# TPS7A.net
KiCad netlist of a schematic drawn in EasyEDA Pro
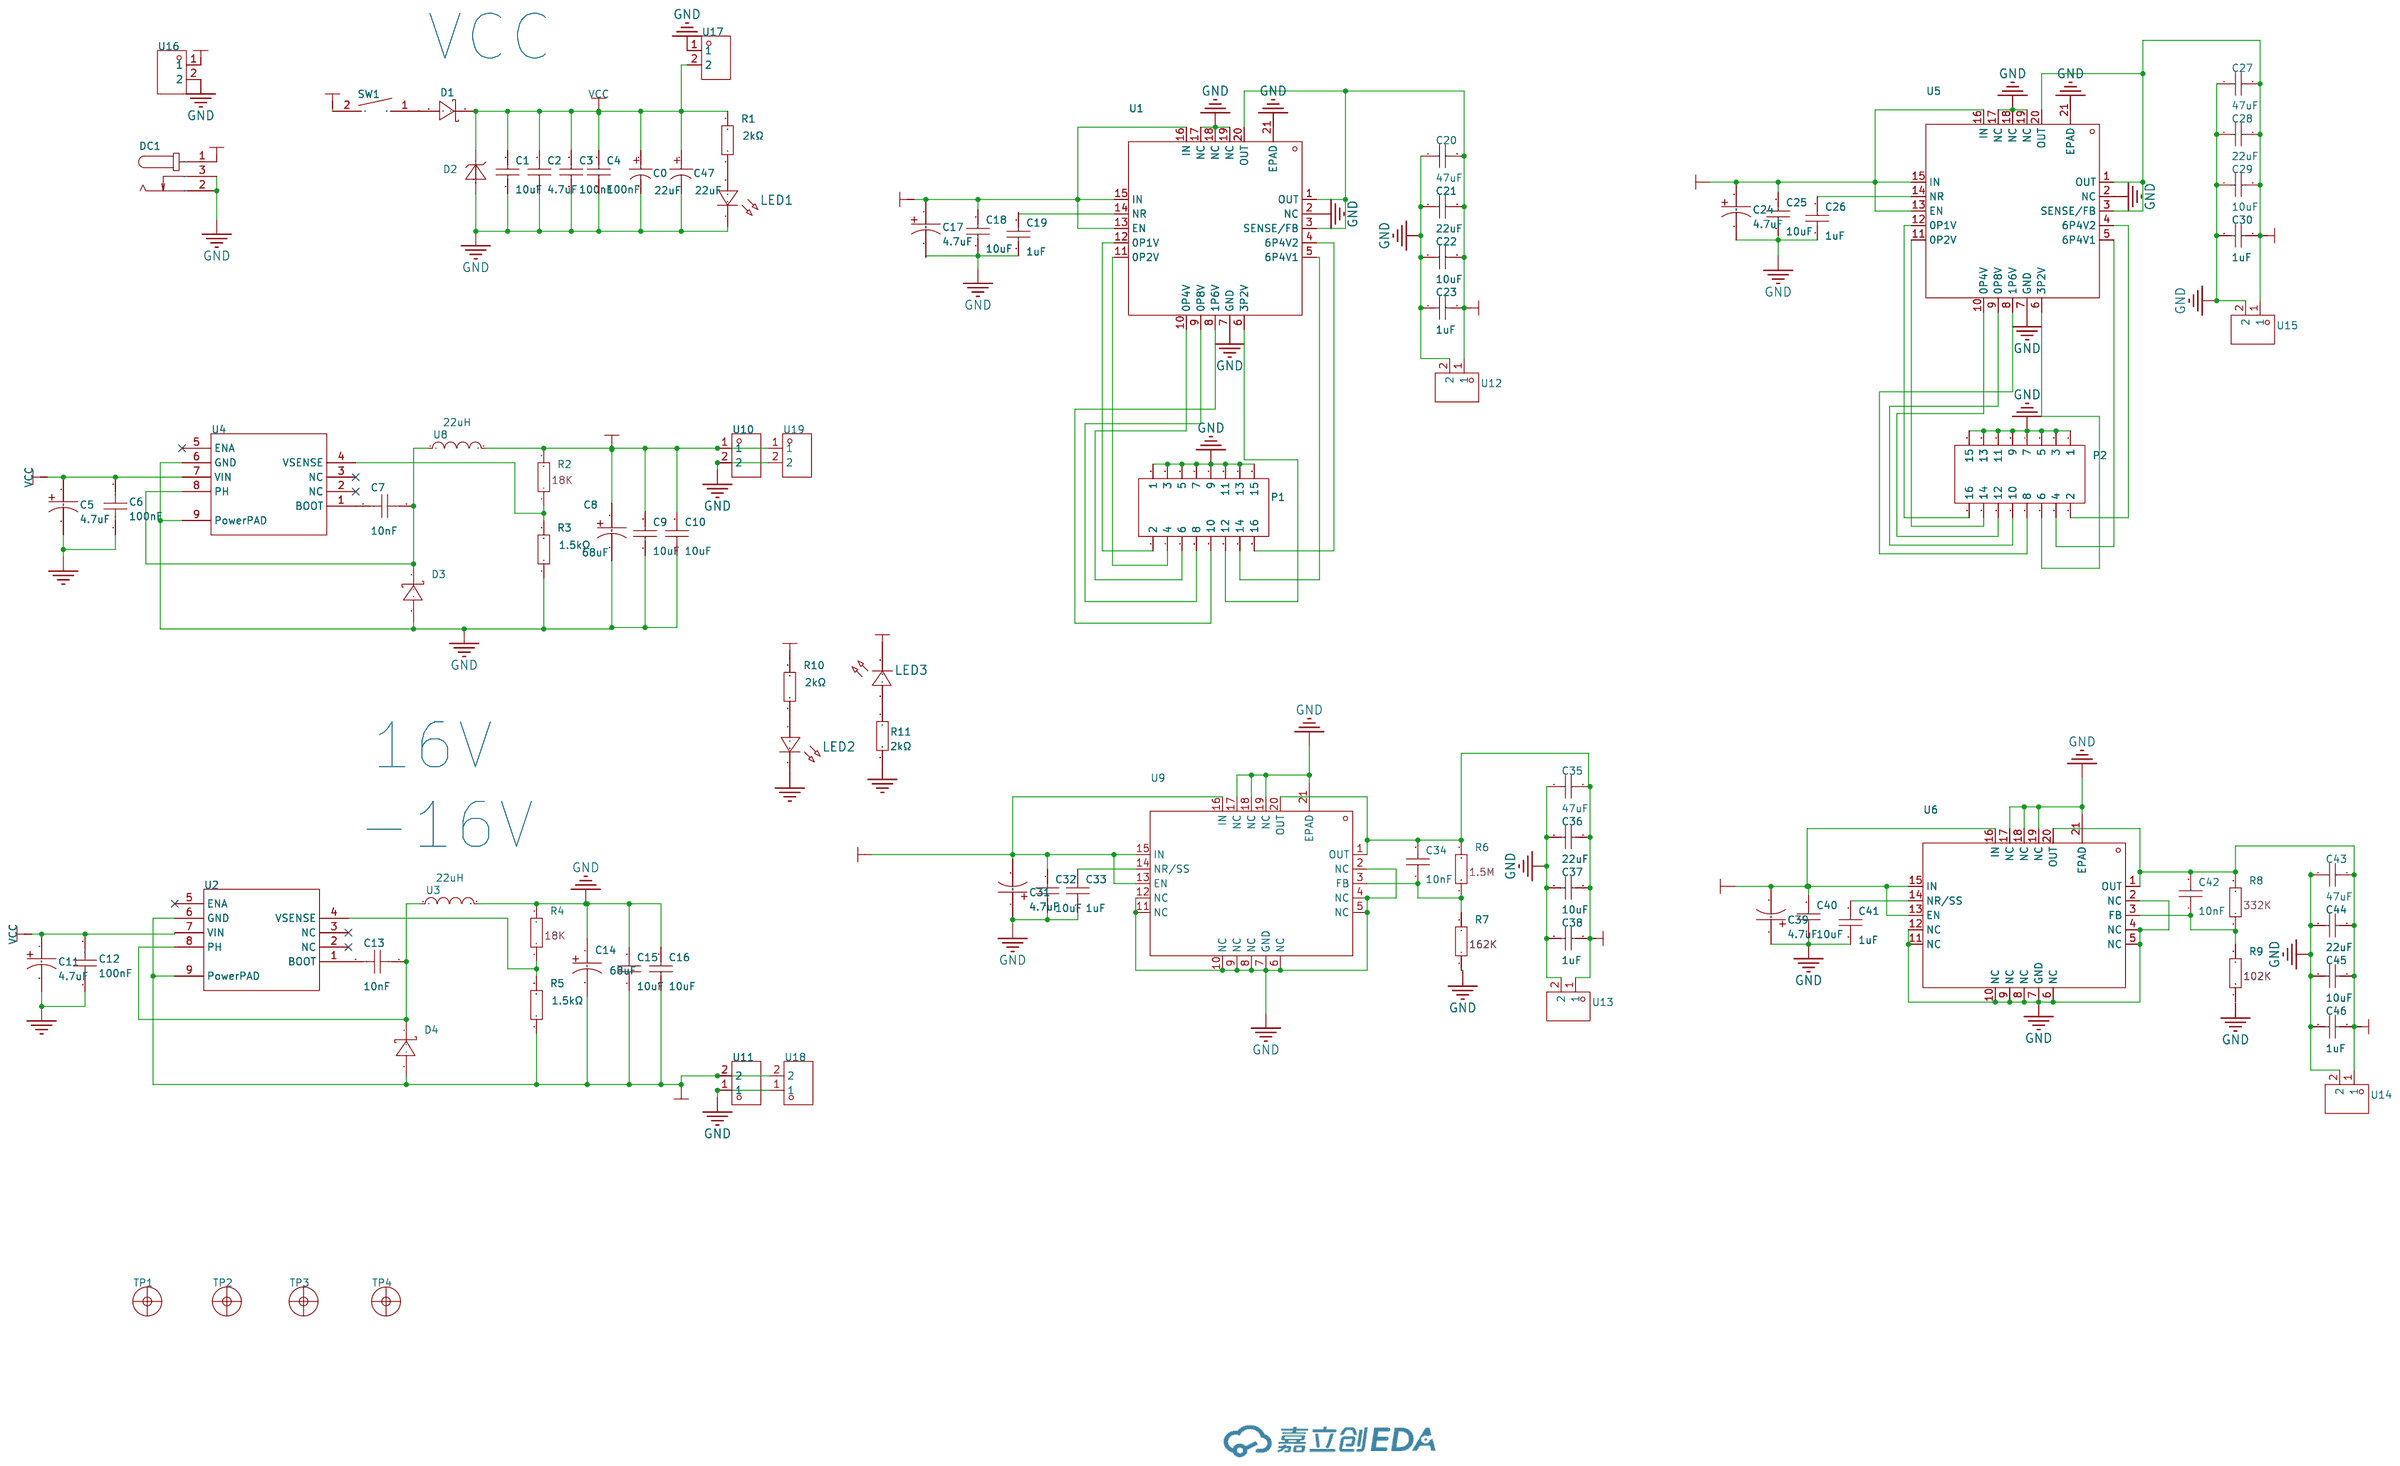
[diagram p0: schematic sheet]

(export (version "E")
  (design (tool "Eeschema 10.0.6"))
  (components
    (comp (ref "C0")
      (value "22uF")
      (footprint "easyedapro:CAP-SMD_BD6.3-L6.6-W6.6-LS7.4-FD")
      (description "容值:22uF;精度:±20%;额定电压:63V;纹波电流:60mA@120Hz;等效串联电阻:-;")
      (fields (field (name "Manufacturer Part") "RT1J220M0607") (field (name "Manufacturer") "ROQANG(容强)"))
      (libsource (lib "easyedapro") (part "RT1J220M0607"))
    )
    (comp (ref "C1")
      (value "10uF")
      (footprint "easyedapro:C0805")
      (description "容值:100nF;精度:±10%;额定电压:50V;材质(温度系数):X7R;")
      (fields (field (name "Manufacturer Part") "0805B104K500NT") (field (name "Manufacturer") "FH(风华)"))
      (libsource (lib "easyedapro") (part "0805B104K500NT"))
    )
    (comp (ref "C2")
      (value "4.7uF")
      (footprint "easyedapro:C0805")
      (description "容值:100nF;精度:±10%;额定电压:50V;材质(温度系数):X7R;")
      (fields (field (name "Manufacturer Part") "0805B104K500NT") (field (name "Manufacturer") "FH(风华)"))
      (libsource (lib "easyedapro") (part "0805B104K500NT"))
    )
    (comp (ref "C3")
      (value "100nF")
      (footprint "easyedapro:C0805")
      (description "容值:100nF;精度:±10%;额定电压:50V;材质(温度系数):X7R;")
      (fields (field (name "Manufacturer Part") "0805B104K500NT") (field (name "Manufacturer") "FH(风华)"))
      (libsource (lib "easyedapro") (part "0805B104K500NT"))
    )
    (comp (ref "C4")
      (value "100nF")
      (footprint "easyedapro:C0805")
      (description "容值:100nF;精度:±10%;额定电压:50V;材质(温度系数):X7R;")
      (fields (field (name "Manufacturer Part") "0805B104K500NT") (field (name "Manufacturer") "FH(风华)"))
      (libsource (lib "easyedapro") (part "0805B104K500NT"))
    )
    (comp (ref "C5")
      (value "4.7uF")
      (footprint "easyedapro:CAP-SMD_BD4.0-L4.3-W4.3-FD-A")
      (description "容值:4.7uF;精度:±20%;额定电压:50V;纹波电流:14mA@120Hz;等效串联电阻:-;")
      (fields (field (name "Manufacturer Part") "VT1H4R7M0405") (field (name "Manufacturer") "ROQANG(容强)"))
      (libsource (lib "easyedapro") (part "VT1H4R7M0405"))
    )
    (comp (ref "C6")
      (value "100nF")
      (footprint "easyedapro:C0805")
      (libsource (lib "easyedapro") (part "CapAcitance"))
    )
    (comp (ref "C7")
      (value "10nF")
      (footprint "easyedapro:C0805")
      (description "容值:10nF;精度:±10%;额定电压:50V;材质(温度系数):X7R;")
      (fields
        (field (name "Manufacturer Part") "CC0805KRX7R9BB103")
        (field (name "Manufacturer") "YAGEO(国巨)")
      )
      (libsource (lib "easyedapro") (part "CC0805KRX7R9BB103"))
    )
    (comp (ref "C8")
      (value "68uF")
      (footprint "easyedapro:CAP-SMD_L7.3-W4.3")
      (description "容值:68uF;精度:±10%;额定电压:25V;等效串联电阻:125mΩ@100kHz;工作温度:-55~+125;")
      (fields
        (field (name "Manufacturer Part") "TPSE686K025R0125")
        (field (name "Manufacturer") "Kyocera AVX")
      )
      (libsource (lib "easyedapro") (part "TPSE686K025R0125"))
    )
    (comp (ref "C9")
      (value "10uF")
      (footprint "easyedapro:C0805")
      (description "容值:100nF;精度:±10%;额定电压:50V;材质(温度系数):X7R;")
      (fields (field (name "Manufacturer Part") "0805B104K500NT") (field (name "Manufacturer") "FH(风华)"))
      (libsource (lib "easyedapro") (part "0805B104K500NT"))
    )
    (comp (ref "C10")
      (value "10uF")
      (footprint "easyedapro:C0805")
      (description "容值:100nF;精度:±10%;额定电压:50V;材质(温度系数):X7R;")
      (fields (field (name "Manufacturer Part") "0805B104K500NT") (field (name "Manufacturer") "FH(风华)"))
      (libsource (lib "easyedapro") (part "0805B104K500NT"))
    )
    (comp (ref "C11")
      (value "4.7uF")
      (footprint "easyedapro:CAP-SMD_BD4.0-L4.3-W4.3-FD-A")
      (description "容值:4.7uF;精度:±20%;额定电压:50V;纹波电流:14mA@120Hz;等效串联电阻:-;")
      (fields (field (name "Manufacturer Part") "VT1H4R7M0405") (field (name "Manufacturer") "ROQANG(容强)"))
      (libsource (lib "easyedapro") (part "VT1H4R7M0405"))
    )
    (comp (ref "C12")
      (value "100nF")
      (footprint "easyedapro:C0805")
      (libsource (lib "easyedapro") (part "CapAcitance"))
    )
    (comp (ref "C13")
      (value "10nF")
      (footprint "easyedapro:C0805")
      (description "容值:10nF;精度:±10%;额定电压:50V;材质(温度系数):X7R;")
      (fields
        (field (name "Manufacturer Part") "CC0805KRX7R9BB103")
        (field (name "Manufacturer") "YAGEO(国巨)")
      )
      (libsource (lib "easyedapro") (part "CC0805KRX7R9BB103"))
    )
    (comp (ref "C14")
      (value "68uF")
      (footprint "easyedapro:CAP-SMD_L7.3-W4.3")
      (description "容值:68uF;精度:±10%;额定电压:25V;等效串联电阻:125mΩ@100kHz;工作温度:-55~+125;")
      (fields
        (field (name "Manufacturer Part") "TPSE686K025R0125")
        (field (name "Manufacturer") "Kyocera AVX")
      )
      (libsource (lib "easyedapro") (part "TPSE686K025R0125"))
    )
    (comp (ref "C15")
      (value "10uF")
      (footprint "easyedapro:C0805")
      (description "容值:100nF;精度:±10%;额定电压:50V;材质(温度系数):X7R;")
      (fields (field (name "Manufacturer Part") "0805B104K500NT") (field (name "Manufacturer") "FH(风华)"))
      (libsource (lib "easyedapro") (part "0805B104K500NT"))
    )
    (comp (ref "C16")
      (value "10uF")
      (footprint "easyedapro:C0805")
      (description "容值:100nF;精度:±10%;额定电压:50V;材质(温度系数):X7R;")
      (fields (field (name "Manufacturer Part") "0805B104K500NT") (field (name "Manufacturer") "FH(风华)"))
      (libsource (lib "easyedapro") (part "0805B104K500NT"))
    )
    (comp (ref "C17")
      (value "4.7uF")
      (footprint "easyedapro:CAP-SMD_BD4.0-L4.3-W4.3-FD-A")
      (description "容值:4.7uF;精度:±20%;额定电压:50V;纹波电流:14mA@120Hz;等效串联电阻:-;")
      (fields (field (name "Manufacturer Part") "VT1H4R7M0405") (field (name "Manufacturer") "ROQANG(容强)"))
      (libsource (lib "easyedapro") (part "VT1H4R7M0405"))
    )
    (comp (ref "C18")
      (value "10uF")
      (footprint "easyedapro:C0805")
      (description "容值:100nF;精度:±10%;额定电压:50V;材质(温度系数):X7R;")
      (fields (field (name "Manufacturer Part") "0805B104K500NT") (field (name "Manufacturer") "FH(风华)"))
      (libsource (lib "easyedapro") (part "0805B104K500NT"))
    )
    (comp (ref "C19")
      (value "1uF")
      (footprint "easyedapro:C0805")
      (description "容值:100nF;精度:±10%;额定电压:50V;材质(温度系数):X7R;")
      (fields (field (name "Manufacturer Part") "0805B104K500NT") (field (name "Manufacturer") "FH(风华)"))
      (libsource (lib "easyedapro") (part "0805B104K500NT"))
    )
    (comp (ref "C20")
      (value "47uF")
      (footprint "easyedapro:C0805")
      (description "容值:100nF;精度:±10%;额定电压:50V;材质(温度系数):X7R;")
      (fields (field (name "Manufacturer Part") "0805B104K500NT") (field (name "Manufacturer") "FH(风华)"))
      (libsource (lib "easyedapro") (part "0805B104K500NT"))
    )
    (comp (ref "C21")
      (value "22uF")
      (footprint "easyedapro:C0805")
      (description "容值:100nF;精度:±10%;额定电压:50V;材质(温度系数):X7R;")
      (fields (field (name "Manufacturer Part") "0805B104K500NT") (field (name "Manufacturer") "FH(风华)"))
      (libsource (lib "easyedapro") (part "0805B104K500NT"))
    )
    (comp (ref "C22")
      (value "10uF")
      (footprint "easyedapro:C0805")
      (description "容值:100nF;精度:±10%;额定电压:50V;材质(温度系数):X7R;")
      (fields (field (name "Manufacturer Part") "0805B104K500NT") (field (name "Manufacturer") "FH(风华)"))
      (libsource (lib "easyedapro") (part "0805B104K500NT"))
    )
    (comp (ref "C23")
      (value "1uF")
      (footprint "easyedapro:C0805")
      (description "容值:100nF;精度:±10%;额定电压:50V;材质(温度系数):X7R;")
      (fields (field (name "Manufacturer Part") "0805B104K500NT") (field (name "Manufacturer") "FH(风华)"))
      (libsource (lib "easyedapro") (part "0805B104K500NT"))
    )
    (comp (ref "C24")
      (value "4.7uF")
      (footprint "easyedapro:CAP-SMD_BD4.0-L4.3-W4.3-FD-A")
      (description "容值:4.7uF;精度:±20%;额定电压:50V;纹波电流:14mA@120Hz;等效串联电阻:-;")
      (fields (field (name "Manufacturer Part") "VT1H4R7M0405") (field (name "Manufacturer") "ROQANG(容强)"))
      (libsource (lib "easyedapro") (part "VT1H4R7M0405"))
    )
    (comp (ref "C25")
      (value "10uF")
      (footprint "easyedapro:C0805")
      (description "容值:100nF;精度:±10%;额定电压:50V;材质(温度系数):X7R;")
      (fields (field (name "Manufacturer Part") "0805B104K500NT") (field (name "Manufacturer") "FH(风华)"))
      (libsource (lib "easyedapro") (part "0805B104K500NT"))
    )
    (comp (ref "C26")
      (value "1uF")
      (footprint "easyedapro:C0805")
      (description "容值:100nF;精度:±10%;额定电压:50V;材质(温度系数):X7R;")
      (fields (field (name "Manufacturer Part") "0805B104K500NT") (field (name "Manufacturer") "FH(风华)"))
      (libsource (lib "easyedapro") (part "0805B104K500NT"))
    )
    (comp (ref "C27")
      (value "47uF")
      (footprint "easyedapro:C0805")
      (description "容值:100nF;精度:±10%;额定电压:50V;材质(温度系数):X7R;")
      (fields (field (name "Manufacturer Part") "0805B104K500NT") (field (name "Manufacturer") "FH(风华)"))
      (libsource (lib "easyedapro") (part "0805B104K500NT"))
    )
    (comp (ref "C28")
      (value "22uF")
      (footprint "easyedapro:C0805")
      (description "容值:100nF;精度:±10%;额定电压:50V;材质(温度系数):X7R;")
      (fields (field (name "Manufacturer Part") "0805B104K500NT") (field (name "Manufacturer") "FH(风华)"))
      (libsource (lib "easyedapro") (part "0805B104K500NT"))
    )
    (comp (ref "C29")
      (value "10uF")
      (footprint "easyedapro:C0805")
      (description "容值:100nF;精度:±10%;额定电压:50V;材质(温度系数):X7R;")
      (fields (field (name "Manufacturer Part") "0805B104K500NT") (field (name "Manufacturer") "FH(风华)"))
      (libsource (lib "easyedapro") (part "0805B104K500NT"))
    )
    (comp (ref "C30")
      (value "1uF")
      (footprint "easyedapro:C0805")
      (description "容值:100nF;精度:±10%;额定电压:50V;材质(温度系数):X7R;")
      (fields (field (name "Manufacturer Part") "0805B104K500NT") (field (name "Manufacturer") "FH(风华)"))
      (libsource (lib "easyedapro") (part "0805B104K500NT"))
    )
    (comp (ref "C31")
      (value "4.7uF")
      (footprint "easyedapro:CAP-SMD_BD4.0-L4.3-W4.3-FD-A")
      (description "容值:4.7uF;精度:±20%;额定电压:50V;纹波电流:14mA@120Hz;等效串联电阻:-;")
      (fields (field (name "Manufacturer Part") "VT1H4R7M0405") (field (name "Manufacturer") "ROQANG(容强)"))
      (libsource (lib "easyedapro") (part "VT1H4R7M0405"))
    )
    (comp (ref "C32")
      (value "10uF")
      (footprint "easyedapro:C0805")
      (description "容值:100nF;精度:±10%;额定电压:50V;材质(温度系数):X7R;")
      (fields (field (name "Manufacturer Part") "0805B104K500NT") (field (name "Manufacturer") "FH(风华)"))
      (libsource (lib "easyedapro") (part "0805B104K500NT"))
    )
    (comp (ref "C33")
      (value "1uF")
      (footprint "easyedapro:C0805")
      (description "容值:100nF;精度:±10%;额定电压:50V;材质(温度系数):X7R;")
      (fields (field (name "Manufacturer Part") "0805B104K500NT") (field (name "Manufacturer") "FH(风华)"))
      (libsource (lib "easyedapro") (part "0805B104K500NT"))
    )
    (comp (ref "C34")
      (value "10nF")
      (footprint "easyedapro:C0805")
      (description "容值:100nF;精度:±10%;额定电压:50V;材质(温度系数):X7R;")
      (fields (field (name "Manufacturer Part") "0805B104K500NT") (field (name "Manufacturer") "FH(风华)"))
      (libsource (lib "easyedapro") (part "0805B104K500NT"))
    )
    (comp (ref "C35")
      (value "47uF")
      (footprint "easyedapro:C0805")
      (description "容值:100nF;精度:±10%;额定电压:50V;材质(温度系数):X7R;")
      (fields (field (name "Manufacturer Part") "0805B104K500NT") (field (name "Manufacturer") "FH(风华)"))
      (libsource (lib "easyedapro") (part "0805B104K500NT"))
    )
    (comp (ref "C36")
      (value "22uF")
      (footprint "easyedapro:C0805")
      (description "容值:100nF;精度:±10%;额定电压:50V;材质(温度系数):X7R;")
      (fields (field (name "Manufacturer Part") "0805B104K500NT") (field (name "Manufacturer") "FH(风华)"))
      (libsource (lib "easyedapro") (part "0805B104K500NT"))
    )
    (comp (ref "C37")
      (value "10uF")
      (footprint "easyedapro:C0805")
      (description "容值:100nF;精度:±10%;额定电压:50V;材质(温度系数):X7R;")
      (fields (field (name "Manufacturer Part") "0805B104K500NT") (field (name "Manufacturer") "FH(风华)"))
      (libsource (lib "easyedapro") (part "0805B104K500NT"))
    )
    (comp (ref "C38")
      (value "1uF")
      (footprint "easyedapro:C0805")
      (description "容值:100nF;精度:±10%;额定电压:50V;材质(温度系数):X7R;")
      (fields (field (name "Manufacturer Part") "0805B104K500NT") (field (name "Manufacturer") "FH(风华)"))
      (libsource (lib "easyedapro") (part "0805B104K500NT"))
    )
    (comp (ref "C39")
      (value "4.7uF")
      (footprint "easyedapro:CAP-SMD_BD4.0-L4.3-W4.3-FD-A")
      (description "容值:4.7uF;精度:±20%;额定电压:50V;纹波电流:14mA@120Hz;等效串联电阻:-;")
      (fields (field (name "Manufacturer Part") "VT1H4R7M0405") (field (name "Manufacturer") "ROQANG(容强)"))
      (libsource (lib "easyedapro") (part "VT1H4R7M0405"))
    )
    (comp (ref "C40")
      (value "10uF")
      (footprint "easyedapro:C0805")
      (description "容值:100nF;精度:±10%;额定电压:50V;材质(温度系数):X7R;")
      (fields (field (name "Manufacturer Part") "0805B104K500NT") (field (name "Manufacturer") "FH(风华)"))
      (libsource (lib "easyedapro") (part "0805B104K500NT"))
    )
    (comp (ref "C41")
      (value "1uF")
      (footprint "easyedapro:C0805")
      (description "容值:100nF;精度:±10%;额定电压:50V;材质(温度系数):X7R;")
      (fields (field (name "Manufacturer Part") "0805B104K500NT") (field (name "Manufacturer") "FH(风华)"))
      (libsource (lib "easyedapro") (part "0805B104K500NT"))
    )
    (comp (ref "C42")
      (value "10nF")
      (footprint "easyedapro:C0805")
      (description "容值:100nF;精度:±10%;额定电压:50V;材质(温度系数):X7R;")
      (fields (field (name "Manufacturer Part") "0805B104K500NT") (field (name "Manufacturer") "FH(风华)"))
      (libsource (lib "easyedapro") (part "0805B104K500NT"))
    )
    (comp (ref "C43")
      (value "47uF")
      (footprint "easyedapro:C0805")
      (description "容值:100nF;精度:±10%;额定电压:50V;材质(温度系数):X7R;")
      (fields (field (name "Manufacturer Part") "0805B104K500NT") (field (name "Manufacturer") "FH(风华)"))
      (libsource (lib "easyedapro") (part "0805B104K500NT"))
    )
    (comp (ref "C44")
      (value "22uF")
      (footprint "easyedapro:C0805")
      (description "容值:100nF;精度:±10%;额定电压:50V;材质(温度系数):X7R;")
      (fields (field (name "Manufacturer Part") "0805B104K500NT") (field (name "Manufacturer") "FH(风华)"))
      (libsource (lib "easyedapro") (part "0805B104K500NT"))
    )
    (comp (ref "C45")
      (value "10uF")
      (footprint "easyedapro:C0805")
      (description "容值:100nF;精度:±10%;额定电压:50V;材质(温度系数):X7R;")
      (fields (field (name "Manufacturer Part") "0805B104K500NT") (field (name "Manufacturer") "FH(风华)"))
      (libsource (lib "easyedapro") (part "0805B104K500NT"))
    )
    (comp (ref "C46")
      (value "1uF")
      (footprint "easyedapro:C0805")
      (description "容值:100nF;精度:±10%;额定电压:50V;材质(温度系数):X7R;")
      (fields (field (name "Manufacturer Part") "0805B104K500NT") (field (name "Manufacturer") "FH(风华)"))
      (libsource (lib "easyedapro") (part "0805B104K500NT"))
    )
    (comp (ref "C47")
      (value "22uF")
      (footprint "easyedapro:CAP-SMD_BD6.3-L6.6-W6.6-LS7.4-FD")
      (description "容值:22uF;精度:±20%;额定电压:63V;纹波电流:60mA@120Hz;等效串联电阻:-;")
      (fields (field (name "Manufacturer Part") "RT1J220M0607") (field (name "Manufacturer") "ROQANG(容强)"))
      (libsource (lib "easyedapro") (part "RT1J220M0607"))
    )
    (comp (ref "D1")
      (value "B340A")
      (footprint "easyedapro:SMA_L4.3-W2.6-LS5.2-RD")
      (description "直流反向耐压(Vr):40V;平均整流电流(Io):3A;正向压降(Vf):550mV@3A;")
      (fields (field (name "Manufacturer") "MDD"))
      (libsource (lib "easyedapro") (part "B340A"))
    )
    (comp (ref "D2")
      (value "SMBJ30A")
      (footprint "easyedapro:SMB_L4.4-W3.6-LS5.3-RD")
      (description "极性:单向;反向截止电压(Vrwm):30V;击穿电压:33.3V;反向漏电流(Ir):5uA;峰值脉冲电流(Ipp)@10/1000s:12.4A;最大钳位电压:48.4V;")
      (fields (field (name "Manufacturer") "GOODWORK(固得沃克)"))
      (libsource (lib "easyedapro") (part "SMBJ30A_C908803"))
    )
    (comp (ref "D3")
      (value "B340A")
      (footprint "easyedapro:SMA_L4.3-W2.6-LS5.2-RD")
      (description "直流反向耐压(Vr):40V;平均整流电流(Io):3A;正向压降(Vf):550mV@3A;")
      (fields (field (name "Manufacturer") "MDD"))
      (libsource (lib "easyedapro") (part "B340A"))
    )
    (comp (ref "D4")
      (value "B340A")
      (footprint "easyedapro:SMA_L4.3-W2.6-LS5.2-RD")
      (description "直流反向耐压(Vr):40V;平均整流电流(Io):3A;正向压降(Vf):550mV@3A;")
      (fields (field (name "Manufacturer") "MDD"))
      (libsource (lib "easyedapro") (part "B340A"))
    )
    (comp (ref "DC1")
      (value "DC005")
      (footprint "easyedapro:DC-IN-TH_DC005")
      (description "连接器类型:DC电源插座;安装方式:弯插;触点内径:2mm;触点外径:6.3mm;额定电流:500mA;额定电压:30V;工作温度范围:-40~+55;")
      (fields (field (name "Manufacturer") "SHOU HAN(首韩)"))
      (libsource (lib "easyedapro") (part "DC005_C431533"))
    )
    (comp (ref "LED1")
      (value "~")
      (footprint "easyedapro:LED_0805")
      (libsource (lib "easyedapro") (part "LED_R"))
    )
    (comp (ref "LED2")
      (value "~")
      (footprint "easyedapro:LED_0805")
      (libsource (lib "easyedapro") (part "LED_R"))
    )
    (comp (ref "LED3")
      (value "~")
      (footprint "easyedapro:LED_0805")
      (libsource (lib "easyedapro") (part "LED_R"))
    )
    (comp (ref "P1")
      (value "2.54-2*8P针")
      (footprint "easyedapro:HDR-TH_16P-P2.54-V-M-R2-C8-S2.54")
      (fields (field (name "Manufacturer") "BOOMELE(博穆精密)"))
      (libsource (lib "easyedapro") (part "Header-Male-2.54_2x8"))
    )
    (comp (ref "P2")
      (value "2.54-2*8P针")
      (footprint "easyedapro:HDR-TH_16P-P2.54-V-M-R2-C8-S2.54")
      (fields (field (name "Manufacturer") "BOOMELE(博穆精密)"))
      (libsource (lib "easyedapro") (part "Header-Male-2.54_2x8"))
    )
    (comp (ref "R1")
      (value "2kΩ")
      (footprint "easyedapro:R0805")
      (description "电阻类型:厚膜电阻;阻值:10kΩ;精度:±1%;功率:125mW;温度系数:±100ppm/;最大工作电压:150V;工作温度范围:-55~+155;")
      (fields
        (field (name "Manufacturer Part") "0805W8F1002T5E")
        (field (name "Manufacturer") "UNI-ROYAL(厚声)")
      )
      (libsource (lib "easyedapro") (part "0805W8F1002T5E"))
    )
    (comp (ref "R2")
      (value "0805W8F9101T5E")
      (footprint "easyedapro:R0805")
      (description "18K")
      (fields (field (name "Manufacturer") "UNI-ROYAL(厚声)"))
      (libsource (lib "easyedapro") (part "0805W8F9101T5E"))
    )
    (comp (ref "R3")
      (value "1.5kΩ")
      (footprint "easyedapro:R0805")
      (description "电阻类型:厚膜电阻;阻值:3kΩ;精度:±1%;功率:125mW;温度系数:±100ppm/;最大工作电压:150V;工作温度范围:-55~+155;")
      (fields
        (field (name "Manufacturer Part") "0805W8F3001T5E")
        (field (name "Manufacturer") "UNI-ROYAL(厚声)")
      )
      (libsource (lib "easyedapro") (part "0805W8F3001T5E"))
    )
    (comp (ref "R4")
      (value "0805W8F9101T5E")
      (footprint "easyedapro:R0805")
      (description "18K")
      (fields (field (name "Manufacturer") "UNI-ROYAL(厚声)"))
      (libsource (lib "easyedapro") (part "0805W8F9101T5E"))
    )
    (comp (ref "R5")
      (value "1.5kΩ")
      (footprint "easyedapro:R0805")
      (description "电阻类型:厚膜电阻;阻值:3kΩ;精度:±1%;功率:125mW;温度系数:±100ppm/;最大工作电压:150V;工作温度范围:-55~+155;")
      (fields
        (field (name "Manufacturer Part") "0805W8F3001T5E")
        (field (name "Manufacturer") "UNI-ROYAL(厚声)")
      )
      (libsource (lib "easyedapro") (part "0805W8F3001T5E"))
    )
    (comp (ref "R6")
      (value "0805W8F9101T5E")
      (footprint "easyedapro:R0805")
      (description "1.5M")
      (fields (field (name "Manufacturer") "UNI-ROYAL(厚声)"))
      (libsource (lib "easyedapro") (part "0805W8F9101T5E"))
    )
    (comp (ref "R7")
      (value "0805W8F9101T5E")
      (footprint "easyedapro:R0805")
      (description "162K")
      (fields (field (name "Manufacturer") "UNI-ROYAL(厚声)"))
      (libsource (lib "easyedapro") (part "0805W8F9101T5E"))
    )
    (comp (ref "R8")
      (value "0805W8F9101T5E")
      (footprint "easyedapro:R0805")
      (description "332K")
      (fields (field (name "Manufacturer") "UNI-ROYAL(厚声)"))
      (libsource (lib "easyedapro") (part "0805W8F9101T5E"))
    )
    (comp (ref "R9")
      (value "0805W8F9101T5E")
      (footprint "easyedapro:R0805")
      (description "102K")
      (fields (field (name "Manufacturer") "UNI-ROYAL(厚声)"))
      (libsource (lib "easyedapro") (part "0805W8F9101T5E"))
    )
    (comp (ref "R10")
      (value "2kΩ")
      (footprint "easyedapro:R0805")
      (description "电阻类型:厚膜电阻;阻值:10kΩ;精度:±1%;功率:125mW;温度系数:±100ppm/;最大工作电压:150V;工作温度范围:-55~+155;")
      (fields
        (field (name "Manufacturer Part") "0805W8F1002T5E")
        (field (name "Manufacturer") "UNI-ROYAL(厚声)")
      )
      (libsource (lib "easyedapro") (part "0805W8F1002T5E"))
    )
    (comp (ref "R11")
      (value "2kΩ")
      (footprint "easyedapro:R0805")
      (description "电阻类型:厚膜电阻;阻值:10kΩ;精度:±1%;功率:125mW;温度系数:±100ppm/;最大工作电压:150V;工作温度范围:-55~+155;")
      (fields
        (field (name "Manufacturer Part") "0805W8F1002T5E")
        (field (name "Manufacturer") "UNI-ROYAL(厚声)")
      )
      (libsource (lib "easyedapro") (part "0805W8F1002T5E"))
    )
    (comp (ref "SW1")
      (value "RS601HL-1010011BB")
      (footprint "easyedapro:SW-TH_RS601HL-1010011BB")
      (fields (field (name "Manufacturer") "HCTL(华灿天禄)"))
      (libsource (lib "easyedapro") (part "RS601HL-1010011BB"))
    )
    (comp (ref "TP1") (value "~") (footprint "easyedapro:M3") (libsource (lib "easyedapro") (part "M3")))
    (comp (ref "TP2") (value "~") (footprint "easyedapro:M3") (libsource (lib "easyedapro") (part "M3")))
    (comp (ref "TP3") (value "~") (footprint "easyedapro:M3") (libsource (lib "easyedapro") (part "M3")))
    (comp (ref "TP4") (value "~") (footprint "easyedapro:M3") (libsource (lib "easyedapro") (part "M3")))
    (comp (ref "U1")
      (value "TPS7A4701RGWR")
      (footprint "easyedapro:VQFN-20_L5.0-W5.0-P0.65-TL-EP")
      (description "输出类型:可调;输出极性:正;最大输入电压:35V;输出电压:1.4V~34V;输出电流:1A;电源纹波抑制比(PSRR):78dB@(1kHz);")
      (fields (field (name "Manufacturer") "TI(德州仪器)"))
      (libsource (lib "easyedapro") (part "TPS7A4701RGWR"))
    )
    (comp (ref "U2")
      (value "TPS5430DDAR")
      (footprint "easyedapro:SOIC-8_L5.0-W4.0-P1.27-LS6.0-BL-EP2.0")
      (description "功能类型:降压型;同步整流:-;输出通道数:-;拓扑结构:-;输入电压:-;输出电流(最大值):-;开关频率:-;")
      (fields (field (name "Manufacturer") "TI(德州仪器)"))
      (libsource (lib "easyedapro") (part "TPS5430DDAR"))
    )
    (comp (ref "U3")
      (value "22uH")
      (footprint "easyedapro:IND-SMD_L7.0-W6.6")
      (description "电感值:6.8uH;精度:±20%;")
      (fields (field (name "Manufacturer Part") "XR0650-6R8M") (field (name "Manufacturer") "XR(祥如)"))
      (libsource (lib "easyedapro") (part "XR0650-6R8M"))
    )
    (comp (ref "U4")
      (value "TPS5430DDAR")
      (footprint "easyedapro:SOIC-8_L5.0-W4.0-P1.27-LS6.0-BL-EP2.0")
      (description "功能类型:降压型;同步整流:-;输出通道数:-;拓扑结构:-;输入电压:-;输出电流(最大值):-;开关频率:-;")
      (fields (field (name "Manufacturer") "TI(德州仪器)"))
      (libsource (lib "easyedapro") (part "TPS5430DDAR"))
    )
    (comp (ref "U5")
      (value "TPS7A4701RGWR")
      (footprint "easyedapro:VQFN-20_L5.0-W5.0-P0.65-TL-EP")
      (description "输出类型:可调;输出极性:正;最大输入电压:35V;输出电压:1.4V~34V;输出电流:1A;电源纹波抑制比(PSRR):78dB@(1kHz);")
      (fields (field (name "Manufacturer") "TI(德州仪器)"))
      (libsource (lib "easyedapro") (part "TPS7A4701RGWR"))
    )
    (comp (ref "U6")
      (value "TPS7A3301RGWR")
      (footprint "easyedapro:VQFN-20_L5.0-W5.0-P0.65-TL-EP")
      (description "输出类型:可调;输出极性:负;最大输入电压:36V;输出电压:1.18V~33V;输出电流:1A;电源纹波抑制比(PSRR):72dB@(10kHz);")
      (fields (field (name "Manufacturer") "TI(德州仪器)"))
      (libsource (lib "easyedapro") (part "TPS7A3301RGWR"))
    )
    (comp (ref "U8")
      (value "22uH")
      (footprint "easyedapro:IND-SMD_L7.0-W6.6")
      (description "电感值:6.8uH;精度:±20%;")
      (fields (field (name "Manufacturer Part") "XR0650-6R8M") (field (name "Manufacturer") "XR(祥如)"))
      (libsource (lib "easyedapro") (part "XR0650-6R8M"))
    )
    (comp (ref "U9")
      (value "TPS7A3301RGWR")
      (footprint "easyedapro:VQFN-20_L5.0-W5.0-P0.65-TL-EP")
      (description "输出类型:可调;输出极性:负;最大输入电压:36V;输出电压:1.18V~33V;输出电流:1A;电源纹波抑制比(PSRR):72dB@(10kHz);")
      (fields (field (name "Manufacturer") "TI(德州仪器)"))
      (libsource (lib "easyedapro") (part "TPS7A3301RGWR"))
    )
    (comp (ref "U10")
      (value "KF301-5.0-2P")
      (footprint "easyedapro:CONN-TH_P5.00_KF301-5.0-2P")
      (fields (field (name "Manufacturer") "KEFA(科发)"))
      (libsource (lib "easyedapro") (part "KF301-5.0-2P"))
    )
    (comp (ref "U11")
      (value "KF301-5.0-2P")
      (footprint "easyedapro:CONN-TH_P5.00_KF301-5.0-2P")
      (fields (field (name "Manufacturer") "KEFA(科发)"))
      (libsource (lib "easyedapro") (part "KF301-5.0-2P"))
    )
    (comp (ref "U12")
      (value "KF301-5.0-2P")
      (footprint "easyedapro:CONN-TH_P5.00_KF301-5.0-2P")
      (fields (field (name "Manufacturer") "KEFA(科发)"))
      (libsource (lib "easyedapro") (part "KF301-5.0-2P"))
    )
    (comp (ref "U13")
      (value "KF301-5.0-2P")
      (footprint "easyedapro:CONN-TH_P5.00_KF301-5.0-2P")
      (fields (field (name "Manufacturer") "KEFA(科发)"))
      (libsource (lib "easyedapro") (part "KF301-5.0-2P"))
    )
    (comp (ref "U14")
      (value "KF301-5.0-2P")
      (footprint "easyedapro:CONN-TH_P5.00_KF301-5.0-2P")
      (fields (field (name "Manufacturer") "KEFA(科发)"))
      (libsource (lib "easyedapro") (part "KF301-5.0-2P"))
    )
    (comp (ref "U15")
      (value "KF301-5.0-2P")
      (footprint "easyedapro:CONN-TH_P5.00_KF301-5.0-2P")
      (fields (field (name "Manufacturer") "KEFA(科发)"))
      (libsource (lib "easyedapro") (part "KF301-5.0-2P"))
    )
    (comp (ref "U16")
      (value "KF301-5.0-2P")
      (footprint "easyedapro:CONN-TH_P5.00_KF301-5.0-2P")
      (fields (field (name "Manufacturer") "KEFA(科发)"))
      (libsource (lib "easyedapro") (part "KF301-5.0-2P"))
    )
    (comp (ref "U17")
      (value "KF301-5.0-2P")
      (footprint "easyedapro:CONN-TH_P5.00_KF301-5.0-2P")
      (fields (field (name "Manufacturer") "KEFA(科发)"))
      (libsource (lib "easyedapro") (part "KF301-5.0-2P"))
    )
    (comp (ref "U18")
      (value "KF301-5.0-2P")
      (footprint "easyedapro:CONN-TH_P5.00_KF301-5.0-2P")
      (fields (field (name "Manufacturer") "KEFA(科发)"))
      (libsource (lib "easyedapro") (part "KF301-5.0-2P"))
    )
    (comp (ref "U19")
      (value "KF301-5.0-2P")
      (footprint "easyedapro:CONN-TH_P5.00_KF301-5.0-2P")
      (fields (field (name "Manufacturer") "KEFA(科发)"))
      (libsource (lib "easyedapro") (part "KF301-5.0-2P"))
    )
  )
  (nets
    (net (code "1") (name "+16V") (class "Default")
      (node (ref "C10") (pin "2") (pinfunction "2_2") (pintype "input"))
      (node (ref "C17") (pin "1") (pinfunction "1_1") (pintype "unspecified"))
      (node (ref "C18") (pin "2") (pinfunction "2_2") (pintype "input"))
      (node (ref "C24") (pin "1") (pinfunction "1_1") (pintype "unspecified"))
      (node (ref "C25") (pin "2") (pinfunction "2_2") (pintype "input"))
      (node (ref "C8") (pin "1") (pinfunction "1_1") (pintype "input"))
      (node (ref "C9") (pin "2") (pinfunction "2_2") (pintype "input"))
      (node (ref "R10") (pin "2") (pinfunction "2_2") (pintype "input"))
      (node (ref "R2") (pin "2") (pinfunction "2_2") (pintype "input"))
      (node (ref "U1") (pin "13") (pinfunction "EN_13") (pintype "input"))
      (node (ref "U1") (pin "15") (pinfunction "IN_15") (pintype "input"))
      (node (ref "U1") (pin "16") (pinfunction "IN_16") (pintype "input"))
      (node (ref "U10") (pin "1") (pinfunction "1_1") (pintype "unspecified"))
      (node (ref "U19") (pin "1") (pinfunction "1_1") (pintype "unspecified"))
      (node (ref "U5") (pin "13") (pinfunction "EN_13") (pintype "input"))
      (node (ref "U5") (pin "15") (pinfunction "IN_15") (pintype "input"))
      (node (ref "U5") (pin "16") (pinfunction "IN_16") (pintype "input"))
      (node (ref "U8") (pin "2") (pinfunction "2_2") (pintype "input"))
    )
    (net (code "2") (name "-16V") (class "Default")
      (node (ref "C14") (pin "2") (pinfunction "2_2") (pintype "input"))
      (node (ref "C15") (pin "1") (pinfunction "1_1") (pintype "input"))
      (node (ref "C16") (pin "1") (pinfunction "1_1") (pintype "input"))
      (node (ref "C31") (pin "2") (pinfunction "2_2") (pintype "unspecified"))
      (node (ref "C32") (pin "2") (pinfunction "2_2") (pintype "input"))
      (node (ref "C39") (pin "2") (pinfunction "2_2") (pintype "unspecified"))
      (node (ref "C40") (pin "2") (pinfunction "2_2") (pintype "input"))
      (node (ref "D4") (pin "2") (pinfunction "A_2") (pintype "input"))
      (node (ref "LED3") (pin "1") (pinfunction "C_1") (pintype "input"))
      (node (ref "R5") (pin "1") (pinfunction "1_1") (pintype "input"))
      (node (ref "U11") (pin "2") (pinfunction "2_2") (pintype "unspecified"))
      (node (ref "U18") (pin "2") (pinfunction "2_2") (pintype "unspecified"))
      (node (ref "U2") (pin "6") (pinfunction "GND_6") (pintype "input"))
      (node (ref "U2") (pin "9") (pinfunction "PowerPAD_9") (pintype "input"))
      (node (ref "U6") (pin "13") (pinfunction "EN_13") (pintype "input"))
      (node (ref "U6") (pin "15") (pinfunction "IN_15") (pintype "input"))
      (node (ref "U6") (pin "16") (pinfunction "IN_16") (pintype "input"))
      (node (ref "U9") (pin "13") (pinfunction "EN_13") (pintype "input"))
      (node (ref "U9") (pin "15") (pinfunction "IN_15") (pintype "input"))
      (node (ref "U9") (pin "16") (pinfunction "IN_16") (pintype "input"))
    )
    (net (code "3") (name "GND") (class "Default")
      (node (ref "C0") (pin "2") (pinfunction "2_2") (pintype "input"))
      (node (ref "C1") (pin "1") (pinfunction "1_1") (pintype "input"))
      (node (ref "C10") (pin "1") (pinfunction "1_1") (pintype "input"))
      (node (ref "C11") (pin "2") (pinfunction "2_2") (pintype "unspecified"))
      (node (ref "C12") (pin "1") (pinfunction "1_1") (pintype "input"))
      (node (ref "C14") (pin "1") (pinfunction "1_1") (pintype "input"))
      (node (ref "C15") (pin "2") (pinfunction "2_2") (pintype "input"))
      (node (ref "C16") (pin "2") (pinfunction "2_2") (pintype "input"))
      (node (ref "C17") (pin "2") (pinfunction "2_2") (pintype "unspecified"))
      (node (ref "C18") (pin "1") (pinfunction "1_1") (pintype "input"))
      (node (ref "C19") (pin "1") (pinfunction "1_1") (pintype "input"))
      (node (ref "C2") (pin "1") (pinfunction "1_1") (pintype "input"))
      (node (ref "C20") (pin "1") (pinfunction "1_1") (pintype "input"))
      (node (ref "C21") (pin "1") (pinfunction "1_1") (pintype "input"))
      (node (ref "C22") (pin "1") (pinfunction "1_1") (pintype "input"))
      (node (ref "C23") (pin "1") (pinfunction "1_1") (pintype "input"))
      (node (ref "C24") (pin "2") (pinfunction "2_2") (pintype "unspecified"))
      (node (ref "C25") (pin "1") (pinfunction "1_1") (pintype "input"))
      (node (ref "C26") (pin "1") (pinfunction "1_1") (pintype "input"))
      (node (ref "C27") (pin "1") (pinfunction "1_1") (pintype "input"))
      (node (ref "C28") (pin "1") (pinfunction "1_1") (pintype "input"))
      (node (ref "C29") (pin "1") (pinfunction "1_1") (pintype "input"))
      (node (ref "C3") (pin "1") (pinfunction "1_1") (pintype "input"))
      (node (ref "C30") (pin "1") (pinfunction "1_1") (pintype "input"))
      (node (ref "C31") (pin "1") (pinfunction "1_1") (pintype "unspecified"))
      (node (ref "C32") (pin "1") (pinfunction "1_1") (pintype "input"))
      (node (ref "C33") (pin "1") (pinfunction "1_1") (pintype "input"))
      (node (ref "C35") (pin "1") (pinfunction "1_1") (pintype "input"))
      (node (ref "C36") (pin "1") (pinfunction "1_1") (pintype "input"))
      (node (ref "C37") (pin "1") (pinfunction "1_1") (pintype "input"))
      (node (ref "C38") (pin "1") (pinfunction "1_1") (pintype "input"))
      (node (ref "C39") (pin "1") (pinfunction "1_1") (pintype "unspecified"))
      (node (ref "C4") (pin "1") (pinfunction "1_1") (pintype "input"))
      (node (ref "C40") (pin "1") (pinfunction "1_1") (pintype "input"))
      (node (ref "C41") (pin "1") (pinfunction "1_1") (pintype "input"))
      (node (ref "C43") (pin "1") (pinfunction "1_1") (pintype "input"))
      (node (ref "C44") (pin "1") (pinfunction "1_1") (pintype "input"))
      (node (ref "C45") (pin "1") (pinfunction "1_1") (pintype "input"))
      (node (ref "C46") (pin "1") (pinfunction "1_1") (pintype "input"))
      (node (ref "C47") (pin "2") (pinfunction "2_2") (pintype "input"))
      (node (ref "C5") (pin "2") (pinfunction "2_2") (pintype "unspecified"))
      (node (ref "C6") (pin "1") (pinfunction "1_1") (pintype "input"))
      (node (ref "C8") (pin "2") (pinfunction "2_2") (pintype "input"))
      (node (ref "C9") (pin "1") (pinfunction "1_1") (pintype "input"))
      (node (ref "D2") (pin "2") (pinfunction "2_2") (pintype "input"))
      (node (ref "D3") (pin "2") (pinfunction "A_2") (pintype "input"))
      (node (ref "DC1") (pin "2") (pinfunction "2_2") (pintype "input"))
      (node (ref "DC1") (pin "3") (pinfunction "3_3") (pintype "input"))
      (node (ref "LED1") (pin "1") (pinfunction "C_1") (pintype "input"))
      (node (ref "LED2") (pin "1") (pinfunction "C_1") (pintype "input"))
      (node (ref "P1") (pin "1") (pinfunction "1_1") (pintype "input"))
      (node (ref "P1") (pin "11") (pinfunction "11_11") (pintype "input"))
      (node (ref "P1") (pin "13") (pinfunction "13_13") (pintype "input"))
      (node (ref "P1") (pin "15") (pinfunction "15_15") (pintype "input"))
      (node (ref "P1") (pin "3") (pinfunction "3_3") (pintype "input"))
      (node (ref "P1") (pin "5") (pinfunction "5_5") (pintype "input"))
      (node (ref "P1") (pin "7") (pinfunction "7_7") (pintype "input"))
      (node (ref "P1") (pin "9") (pinfunction "9_9") (pintype "input"))
      (node (ref "P2") (pin "1") (pinfunction "1_1") (pintype "input"))
      (node (ref "P2") (pin "11") (pinfunction "11_11") (pintype "input"))
      (node (ref "P2") (pin "13") (pinfunction "13_13") (pintype "input"))
      (node (ref "P2") (pin "15") (pinfunction "15_15") (pintype "input"))
      (node (ref "P2") (pin "3") (pinfunction "3_3") (pintype "input"))
      (node (ref "P2") (pin "5") (pinfunction "5_5") (pintype "input"))
      (node (ref "P2") (pin "7") (pinfunction "7_7") (pintype "input"))
      (node (ref "P2") (pin "9") (pinfunction "9_9") (pintype "input"))
      (node (ref "R11") (pin "2") (pinfunction "2_2") (pintype "input"))
      (node (ref "R3") (pin "1") (pinfunction "1_1") (pintype "input"))
      (node (ref "R4") (pin "2") (pinfunction "2_2") (pintype "input"))
      (node (ref "R7") (pin "1") (pinfunction "1_1") (pintype "input"))
      (node (ref "R9") (pin "1") (pinfunction "1_1") (pintype "input"))
      (node (ref "U1") (pin "17") (pinfunction "NC_17") (pintype "input"))
      (node (ref "U1") (pin "18") (pinfunction "NC_18") (pintype "input"))
      (node (ref "U1") (pin "19") (pinfunction "NC_19") (pintype "input"))
      (node (ref "U1") (pin "2") (pinfunction "NC_2") (pintype "input"))
      (node (ref "U1") (pin "21") (pinfunction "EPAD_21") (pintype "input"))
      (node (ref "U1") (pin "7") (pinfunction "GND_7") (pintype "input"))
      (node (ref "U10") (pin "2") (pinfunction "2_2") (pintype "unspecified"))
      (node (ref "U11") (pin "1") (pinfunction "1_1") (pintype "unspecified"))
      (node (ref "U12") (pin "2") (pinfunction "2_2") (pintype "unspecified"))
      (node (ref "U13") (pin "2") (pinfunction "2_2") (pintype "unspecified"))
      (node (ref "U14") (pin "2") (pinfunction "2_2") (pintype "unspecified"))
      (node (ref "U15") (pin "2") (pinfunction "2_2") (pintype "unspecified"))
      (node (ref "U16") (pin "2") (pinfunction "2_2") (pintype "unspecified"))
      (node (ref "U17") (pin "1") (pinfunction "1_1") (pintype "unspecified"))
      (node (ref "U18") (pin "1") (pinfunction "1_1") (pintype "unspecified"))
      (node (ref "U19") (pin "2") (pinfunction "2_2") (pintype "unspecified"))
      (node (ref "U3") (pin "2") (pinfunction "2_2") (pintype "input"))
      (node (ref "U4") (pin "6") (pinfunction "GND_6") (pintype "input"))
      (node (ref "U4") (pin "9") (pinfunction "PowerPAD_9") (pintype "input"))
      (node (ref "U5") (pin "17") (pinfunction "NC_17") (pintype "input"))
      (node (ref "U5") (pin "18") (pinfunction "NC_18") (pintype "input"))
      (node (ref "U5") (pin "19") (pinfunction "NC_19") (pintype "input"))
      (node (ref "U5") (pin "2") (pinfunction "NC_2") (pintype "input"))
      (node (ref "U5") (pin "21") (pinfunction "EPAD_21") (pintype "input"))
      (node (ref "U5") (pin "7") (pinfunction "GND_7") (pintype "input"))
      (node (ref "U6") (pin "10") (pinfunction "NC_10") (pintype "input"))
      (node (ref "U6") (pin "11") (pinfunction "NC_11") (pintype "input"))
      (node (ref "U6") (pin "12") (pinfunction "NC_12") (pintype "input"))
      (node (ref "U6") (pin "17") (pinfunction "NC_17") (pintype "input"))
      (node (ref "U6") (pin "18") (pinfunction "NC_18") (pintype "input"))
      (node (ref "U6") (pin "19") (pinfunction "NC_19") (pintype "input"))
      (node (ref "U6") (pin "2") (pinfunction "NC_2") (pintype "input"))
      (node (ref "U6") (pin "21") (pinfunction "EPAD_21") (pintype "input"))
      (node (ref "U6") (pin "4") (pinfunction "NC_4") (pintype "input"))
      (node (ref "U6") (pin "5") (pinfunction "NC_5") (pintype "input"))
      (node (ref "U6") (pin "6") (pinfunction "NC_6") (pintype "input"))
      (node (ref "U6") (pin "7") (pinfunction "GND_7") (pintype "input"))
      (node (ref "U6") (pin "8") (pinfunction "NC_8") (pintype "input"))
      (node (ref "U6") (pin "9") (pinfunction "NC_9") (pintype "input"))
      (node (ref "U9") (pin "10") (pinfunction "NC_10") (pintype "input"))
      (node (ref "U9") (pin "11") (pinfunction "NC_11") (pintype "input"))
      (node (ref "U9") (pin "12") (pinfunction "NC_12") (pintype "input"))
      (node (ref "U9") (pin "17") (pinfunction "NC_17") (pintype "input"))
      (node (ref "U9") (pin "18") (pinfunction "NC_18") (pintype "input"))
      (node (ref "U9") (pin "19") (pinfunction "NC_19") (pintype "input"))
      (node (ref "U9") (pin "2") (pinfunction "NC_2") (pintype "input"))
      (node (ref "U9") (pin "21") (pinfunction "EPAD_21") (pintype "input"))
      (node (ref "U9") (pin "4") (pinfunction "NC_4") (pintype "input"))
      (node (ref "U9") (pin "5") (pinfunction "NC_5") (pintype "input"))
      (node (ref "U9") (pin "6") (pinfunction "NC_6") (pintype "input"))
      (node (ref "U9") (pin "7") (pinfunction "GND_7") (pintype "input"))
      (node (ref "U9") (pin "8") (pinfunction "NC_8") (pintype "input"))
      (node (ref "U9") (pin "9") (pinfunction "NC_9") (pintype "input"))
    )
    (net (code "4") (name "Net-(D1-A)") (class "Default")
      (node (ref "D1") (pin "2") (pinfunction "A_2") (pintype "input"))
      (node (ref "SW1") (pin "1") (pinfunction "1_1") (pintype "input"))
    )
    (net (code "5") (name "Net-(D3-K)") (class "Default")
      (node (ref "C7") (pin "1") (pinfunction "1_1") (pintype "input"))
      (node (ref "D3") (pin "1") (pinfunction "K_1") (pintype "input"))
      (node (ref "U4") (pin "8") (pinfunction "PH_8") (pintype "input"))
      (node (ref "U8") (pin "1") (pinfunction "1_1") (pintype "input"))
    )
    (net (code "6") (name "Net-(D4-K)") (class "Default")
      (node (ref "C13") (pin "1") (pinfunction "1_1") (pintype "input"))
      (node (ref "D4") (pin "1") (pinfunction "K_1") (pintype "input"))
      (node (ref "U2") (pin "8") (pinfunction "PH_8") (pintype "input"))
      (node (ref "U3") (pin "1") (pinfunction "1_1") (pintype "input"))
    )
    (net (code "7") (name "Net-(LED1-A)") (class "Default")
      (node (ref "LED1") (pin "2") (pinfunction "A_2") (pintype "input"))
      (node (ref "R1") (pin "1") (pinfunction "1_1") (pintype "input"))
    )
    (net (code "8") (name "Net-(LED2-A)") (class "Default")
      (node (ref "LED2") (pin "2") (pinfunction "A_2") (pintype "input"))
      (node (ref "R10") (pin "1") (pinfunction "1_1") (pintype "input"))
    )
    (net (code "9") (name "Net-(LED3-A)") (class "Default")
      (node (ref "LED3") (pin "2") (pinfunction "A_2") (pintype "input"))
      (node (ref "R11") (pin "1") (pinfunction "1_1") (pintype "input"))
    )
    (net (code "10") (name "Net-(U1-0P1V)") (class "Default")
      (node (ref "P1") (pin "2") (pinfunction "2_2") (pintype "input"))
      (node (ref "U1") (pin "12") (pinfunction "0P1V_12") (pintype "input"))
    )
    (net (code "11") (name "Net-(U1-0P2V)") (class "Default")
      (node (ref "P1") (pin "4") (pinfunction "4_4") (pintype "input"))
      (node (ref "U1") (pin "11") (pinfunction "0P2V_11") (pintype "input"))
    )
    (net (code "12") (name "Net-(U1-0P4V)") (class "Default")
      (node (ref "P1") (pin "6") (pinfunction "6_6") (pintype "input"))
      (node (ref "U1") (pin "10") (pinfunction "0P4V_10") (pintype "input"))
    )
    (net (code "13") (name "Net-(U1-0P8V)") (class "Default")
      (node (ref "P1") (pin "8") (pinfunction "8_8") (pintype "input"))
      (node (ref "U1") (pin "9") (pinfunction "0P8V_9") (pintype "input"))
    )
    (net (code "14") (name "Net-(U1-1P6V)") (class "Default")
      (node (ref "P1") (pin "10") (pinfunction "10_10") (pintype "input"))
      (node (ref "U1") (pin "8") (pinfunction "1P6V_8") (pintype "input"))
    )
    (net (code "15") (name "Net-(U1-3P2V)") (class "Default")
      (node (ref "P1") (pin "12") (pinfunction "12_12") (pintype "input"))
      (node (ref "U1") (pin "6") (pinfunction "3P2V_6") (pintype "input"))
    )
    (net (code "16") (name "Net-(U1-6P4V1)") (class "Default")
      (node (ref "P1") (pin "14") (pinfunction "14_14") (pintype "input"))
      (node (ref "U1") (pin "5") (pinfunction "6P4V1_5") (pintype "input"))
    )
    (net (code "17") (name "Net-(U1-6P4V2)") (class "Default")
      (node (ref "P1") (pin "16") (pinfunction "16_16") (pintype "input"))
      (node (ref "U1") (pin "4") (pinfunction "6P4V2_4") (pintype "input"))
    )
    (net (code "18") (name "Net-(U1-NR)") (class "Default")
      (node (ref "C19") (pin "2") (pinfunction "2_2") (pintype "input"))
      (node (ref "U1") (pin "14") (pinfunction "NR_14") (pintype "input"))
    )
    (net (code "19") (name "Net-(U2-BOOT)") (class "Default")
      (node (ref "C13") (pin "2") (pinfunction "2_2") (pintype "input"))
      (node (ref "U2") (pin "1") (pinfunction "BOOT_1") (pintype "input"))
    )
    (net (code "20") (name "Net-(U2-VSENSE)") (class "Default")
      (node (ref "R4") (pin "1") (pinfunction "1_1") (pintype "input"))
      (node (ref "R5") (pin "2") (pinfunction "2_2") (pintype "input"))
      (node (ref "U2") (pin "4") (pinfunction "VSENSE_4") (pintype "input"))
    )
    (net (code "21") (name "Net-(U4-BOOT)") (class "Default")
      (node (ref "C7") (pin "2") (pinfunction "2_2") (pintype "input"))
      (node (ref "U4") (pin "1") (pinfunction "BOOT_1") (pintype "input"))
    )
    (net (code "22") (name "Net-(U4-VSENSE)") (class "Default")
      (node (ref "R2") (pin "1") (pinfunction "1_1") (pintype "input"))
      (node (ref "R3") (pin "2") (pinfunction "2_2") (pintype "input"))
      (node (ref "U4") (pin "4") (pinfunction "VSENSE_4") (pintype "input"))
    )
    (net (code "23") (name "Net-(U5-0P1V)") (class "Default")
      (node (ref "P2") (pin "16") (pinfunction "16_16") (pintype "input"))
      (node (ref "U5") (pin "12") (pinfunction "0P1V_12") (pintype "input"))
    )
    (net (code "24") (name "Net-(U5-0P2V)") (class "Default")
      (node (ref "P2") (pin "14") (pinfunction "14_14") (pintype "input"))
      (node (ref "U5") (pin "11") (pinfunction "0P2V_11") (pintype "input"))
    )
    (net (code "25") (name "Net-(U5-0P4V)") (class "Default")
      (node (ref "P2") (pin "12") (pinfunction "12_12") (pintype "input"))
      (node (ref "U5") (pin "10") (pinfunction "0P4V_10") (pintype "input"))
    )
    (net (code "26") (name "Net-(U5-0P8V)") (class "Default")
      (node (ref "P2") (pin "10") (pinfunction "10_10") (pintype "input"))
      (node (ref "U5") (pin "9") (pinfunction "0P8V_9") (pintype "input"))
    )
    (net (code "27") (name "Net-(U5-1P6V)") (class "Default")
      (node (ref "P2") (pin "8") (pinfunction "8_8") (pintype "input"))
      (node (ref "U5") (pin "8") (pinfunction "1P6V_8") (pintype "input"))
    )
    (net (code "28") (name "Net-(U5-3P2V)") (class "Default")
      (node (ref "P2") (pin "6") (pinfunction "6_6") (pintype "input"))
      (node (ref "U5") (pin "6") (pinfunction "3P2V_6") (pintype "input"))
    )
    (net (code "29") (name "Net-(U5-6P4V1)") (class "Default")
      (node (ref "P2") (pin "4") (pinfunction "4_4") (pintype "input"))
      (node (ref "U5") (pin "5") (pinfunction "6P4V1_5") (pintype "input"))
    )
    (net (code "30") (name "Net-(U5-6P4V2)") (class "Default")
      (node (ref "P2") (pin "2") (pinfunction "2_2") (pintype "input"))
      (node (ref "U5") (pin "4") (pinfunction "6P4V2_4") (pintype "input"))
    )
    (net (code "31") (name "Net-(U5-NR)") (class "Default")
      (node (ref "C26") (pin "2") (pinfunction "2_2") (pintype "input"))
      (node (ref "U5") (pin "14") (pinfunction "NR_14") (pintype "input"))
    )
    (net (code "32") (name "Net-(U6-FB)") (class "Default")
      (node (ref "C42") (pin "1") (pinfunction "1_1") (pintype "input"))
      (node (ref "R8") (pin "1") (pinfunction "1_1") (pintype "input"))
      (node (ref "R9") (pin "2") (pinfunction "2_2") (pintype "input"))
      (node (ref "U6") (pin "3") (pinfunction "FB_3") (pintype "input"))
    )
    (net (code "33") (name "Net-(U6-NR{slash}SS)") (class "Default")
      (node (ref "C41") (pin "2") (pinfunction "2_2") (pintype "input"))
      (node (ref "U6") (pin "14") (pinfunction "NR/SS_14") (pintype "input"))
    )
    (net (code "34") (name "Net-(U9-FB)") (class "Default")
      (node (ref "C34") (pin "1") (pinfunction "1_1") (pintype "input"))
      (node (ref "R6") (pin "1") (pinfunction "1_1") (pintype "input"))
      (node (ref "R7") (pin "2") (pinfunction "2_2") (pintype "input"))
      (node (ref "U9") (pin "3") (pinfunction "FB_3") (pintype "input"))
    )
    (net (code "35") (name "Net-(U9-NR{slash}SS)") (class "Default")
      (node (ref "C33") (pin "2") (pinfunction "2_2") (pintype "input"))
      (node (ref "U9") (pin "14") (pinfunction "NR/SS_14") (pintype "input"))
    )
    (net (code "36") (name "OUT1+") (class "Default")
      (node (ref "C20") (pin "2") (pinfunction "2_2") (pintype "input"))
      (node (ref "C21") (pin "2") (pinfunction "2_2") (pintype "input"))
      (node (ref "C22") (pin "2") (pinfunction "2_2") (pintype "input"))
      (node (ref "C23") (pin "2") (pinfunction "2_2") (pintype "input"))
      (node (ref "U1") (pin "1") (pinfunction "OUT_1") (pintype "input"))
      (node (ref "U1") (pin "20") (pinfunction "OUT_20") (pintype "input"))
      (node (ref "U1") (pin "3") (pinfunction "SENSE/FB_3") (pintype "input"))
      (node (ref "U12") (pin "1") (pinfunction "1_1") (pintype "unspecified"))
    )
    (net (code "37") (name "OUT1-") (class "Default")
      (node (ref "C34") (pin "2") (pinfunction "2_2") (pintype "input"))
      (node (ref "C35") (pin "2") (pinfunction "2_2") (pintype "input"))
      (node (ref "C36") (pin "2") (pinfunction "2_2") (pintype "input"))
      (node (ref "C37") (pin "2") (pinfunction "2_2") (pintype "input"))
      (node (ref "C38") (pin "2") (pinfunction "2_2") (pintype "input"))
      (node (ref "R6") (pin "2") (pinfunction "2_2") (pintype "input"))
      (node (ref "U13") (pin "1") (pinfunction "1_1") (pintype "unspecified"))
      (node (ref "U9") (pin "1") (pinfunction "OUT_1") (pintype "input"))
      (node (ref "U9") (pin "20") (pinfunction "OUT_20") (pintype "input"))
    )
    (net (code "38") (name "OUT2+") (class "Default")
      (node (ref "C27") (pin "2") (pinfunction "2_2") (pintype "input"))
      (node (ref "C28") (pin "2") (pinfunction "2_2") (pintype "input"))
      (node (ref "C29") (pin "2") (pinfunction "2_2") (pintype "input"))
      (node (ref "C30") (pin "2") (pinfunction "2_2") (pintype "input"))
      (node (ref "U15") (pin "1") (pinfunction "1_1") (pintype "unspecified"))
      (node (ref "U5") (pin "1") (pinfunction "OUT_1") (pintype "input"))
      (node (ref "U5") (pin "20") (pinfunction "OUT_20") (pintype "input"))
      (node (ref "U5") (pin "3") (pinfunction "SENSE/FB_3") (pintype "input"))
    )
    (net (code "39") (name "OUT2-") (class "Default")
      (node (ref "C42") (pin "2") (pinfunction "2_2") (pintype "input"))
      (node (ref "C43") (pin "2") (pinfunction "2_2") (pintype "input"))
      (node (ref "C44") (pin "2") (pinfunction "2_2") (pintype "input"))
      (node (ref "C45") (pin "2") (pinfunction "2_2") (pintype "input"))
      (node (ref "C46") (pin "2") (pinfunction "2_2") (pintype "input"))
      (node (ref "R8") (pin "2") (pinfunction "2_2") (pintype "input"))
      (node (ref "U14") (pin "1") (pinfunction "1_1") (pintype "unspecified"))
      (node (ref "U6") (pin "1") (pinfunction "OUT_1") (pintype "input"))
      (node (ref "U6") (pin "20") (pinfunction "OUT_20") (pintype "input"))
    )
    (net (code "40") (name "VCC") (class "Default")
      (node (ref "C0") (pin "1") (pinfunction "1_1") (pintype "input"))
      (node (ref "C1") (pin "2") (pinfunction "2_2") (pintype "input"))
      (node (ref "C11") (pin "1") (pinfunction "1_1") (pintype "unspecified"))
      (node (ref "C12") (pin "2") (pinfunction "2_2") (pintype "input"))
      (node (ref "C2") (pin "2") (pinfunction "2_2") (pintype "input"))
      (node (ref "C3") (pin "2") (pinfunction "2_2") (pintype "input"))
      (node (ref "C4") (pin "2") (pinfunction "2_2") (pintype "input"))
      (node (ref "C47") (pin "1") (pinfunction "1_1") (pintype "input"))
      (node (ref "C5") (pin "1") (pinfunction "1_1") (pintype "unspecified"))
      (node (ref "C6") (pin "2") (pinfunction "2_2") (pintype "input"))
      (node (ref "D1") (pin "1") (pinfunction "K_1") (pintype "input"))
      (node (ref "D2") (pin "1") (pinfunction "1_1") (pintype "input"))
      (node (ref "R1") (pin "2") (pinfunction "2_2") (pintype "input"))
      (node (ref "U17") (pin "2") (pinfunction "2_2") (pintype "unspecified"))
      (node (ref "U2") (pin "7") (pinfunction "VIN_7") (pintype "input"))
      (node (ref "U4") (pin "7") (pinfunction "VIN_7") (pintype "input"))
    )
    (net (code "41") (name "VIN") (class "Default")
      (node (ref "DC1") (pin "1") (pinfunction "1_1") (pintype "input"))
      (node (ref "SW1") (pin "2") (pinfunction "2_2") (pintype "input"))
      (node (ref "U16") (pin "1") (pinfunction "1_1") (pintype "unspecified"))
    )
    (net (code "42") (name "unconnected-(U2-ENA-Pad5)") (class "Default")
      (node (ref "U2") (pin "5") (pinfunction "ENA_5") (pintype "input+no_connect"))
    )
    (net (code "43") (name "unconnected-(U2-NC-Pad2)") (class "Default")
      (node (ref "U2") (pin "2") (pinfunction "NC_2") (pintype "input+no_connect"))
    )
    (net (code "44") (name "unconnected-(U2-NC-Pad3)") (class "Default")
      (node (ref "U2") (pin "3") (pinfunction "NC_3") (pintype "input+no_connect"))
    )
    (net (code "45") (name "unconnected-(U4-ENA-Pad5)") (class "Default")
      (node (ref "U4") (pin "5") (pinfunction "ENA_5") (pintype "input+no_connect"))
    )
    (net (code "46") (name "unconnected-(U4-NC-Pad2)") (class "Default")
      (node (ref "U4") (pin "2") (pinfunction "NC_2") (pintype "input+no_connect"))
    )
    (net (code "47") (name "unconnected-(U4-NC-Pad3)") (class "Default")
      (node (ref "U4") (pin "3") (pinfunction "NC_3") (pintype "input+no_connect"))
    )
  )
)
